# CONNECTOR_B.net
KiCad netlist of a schematic drawn in Altium Designer
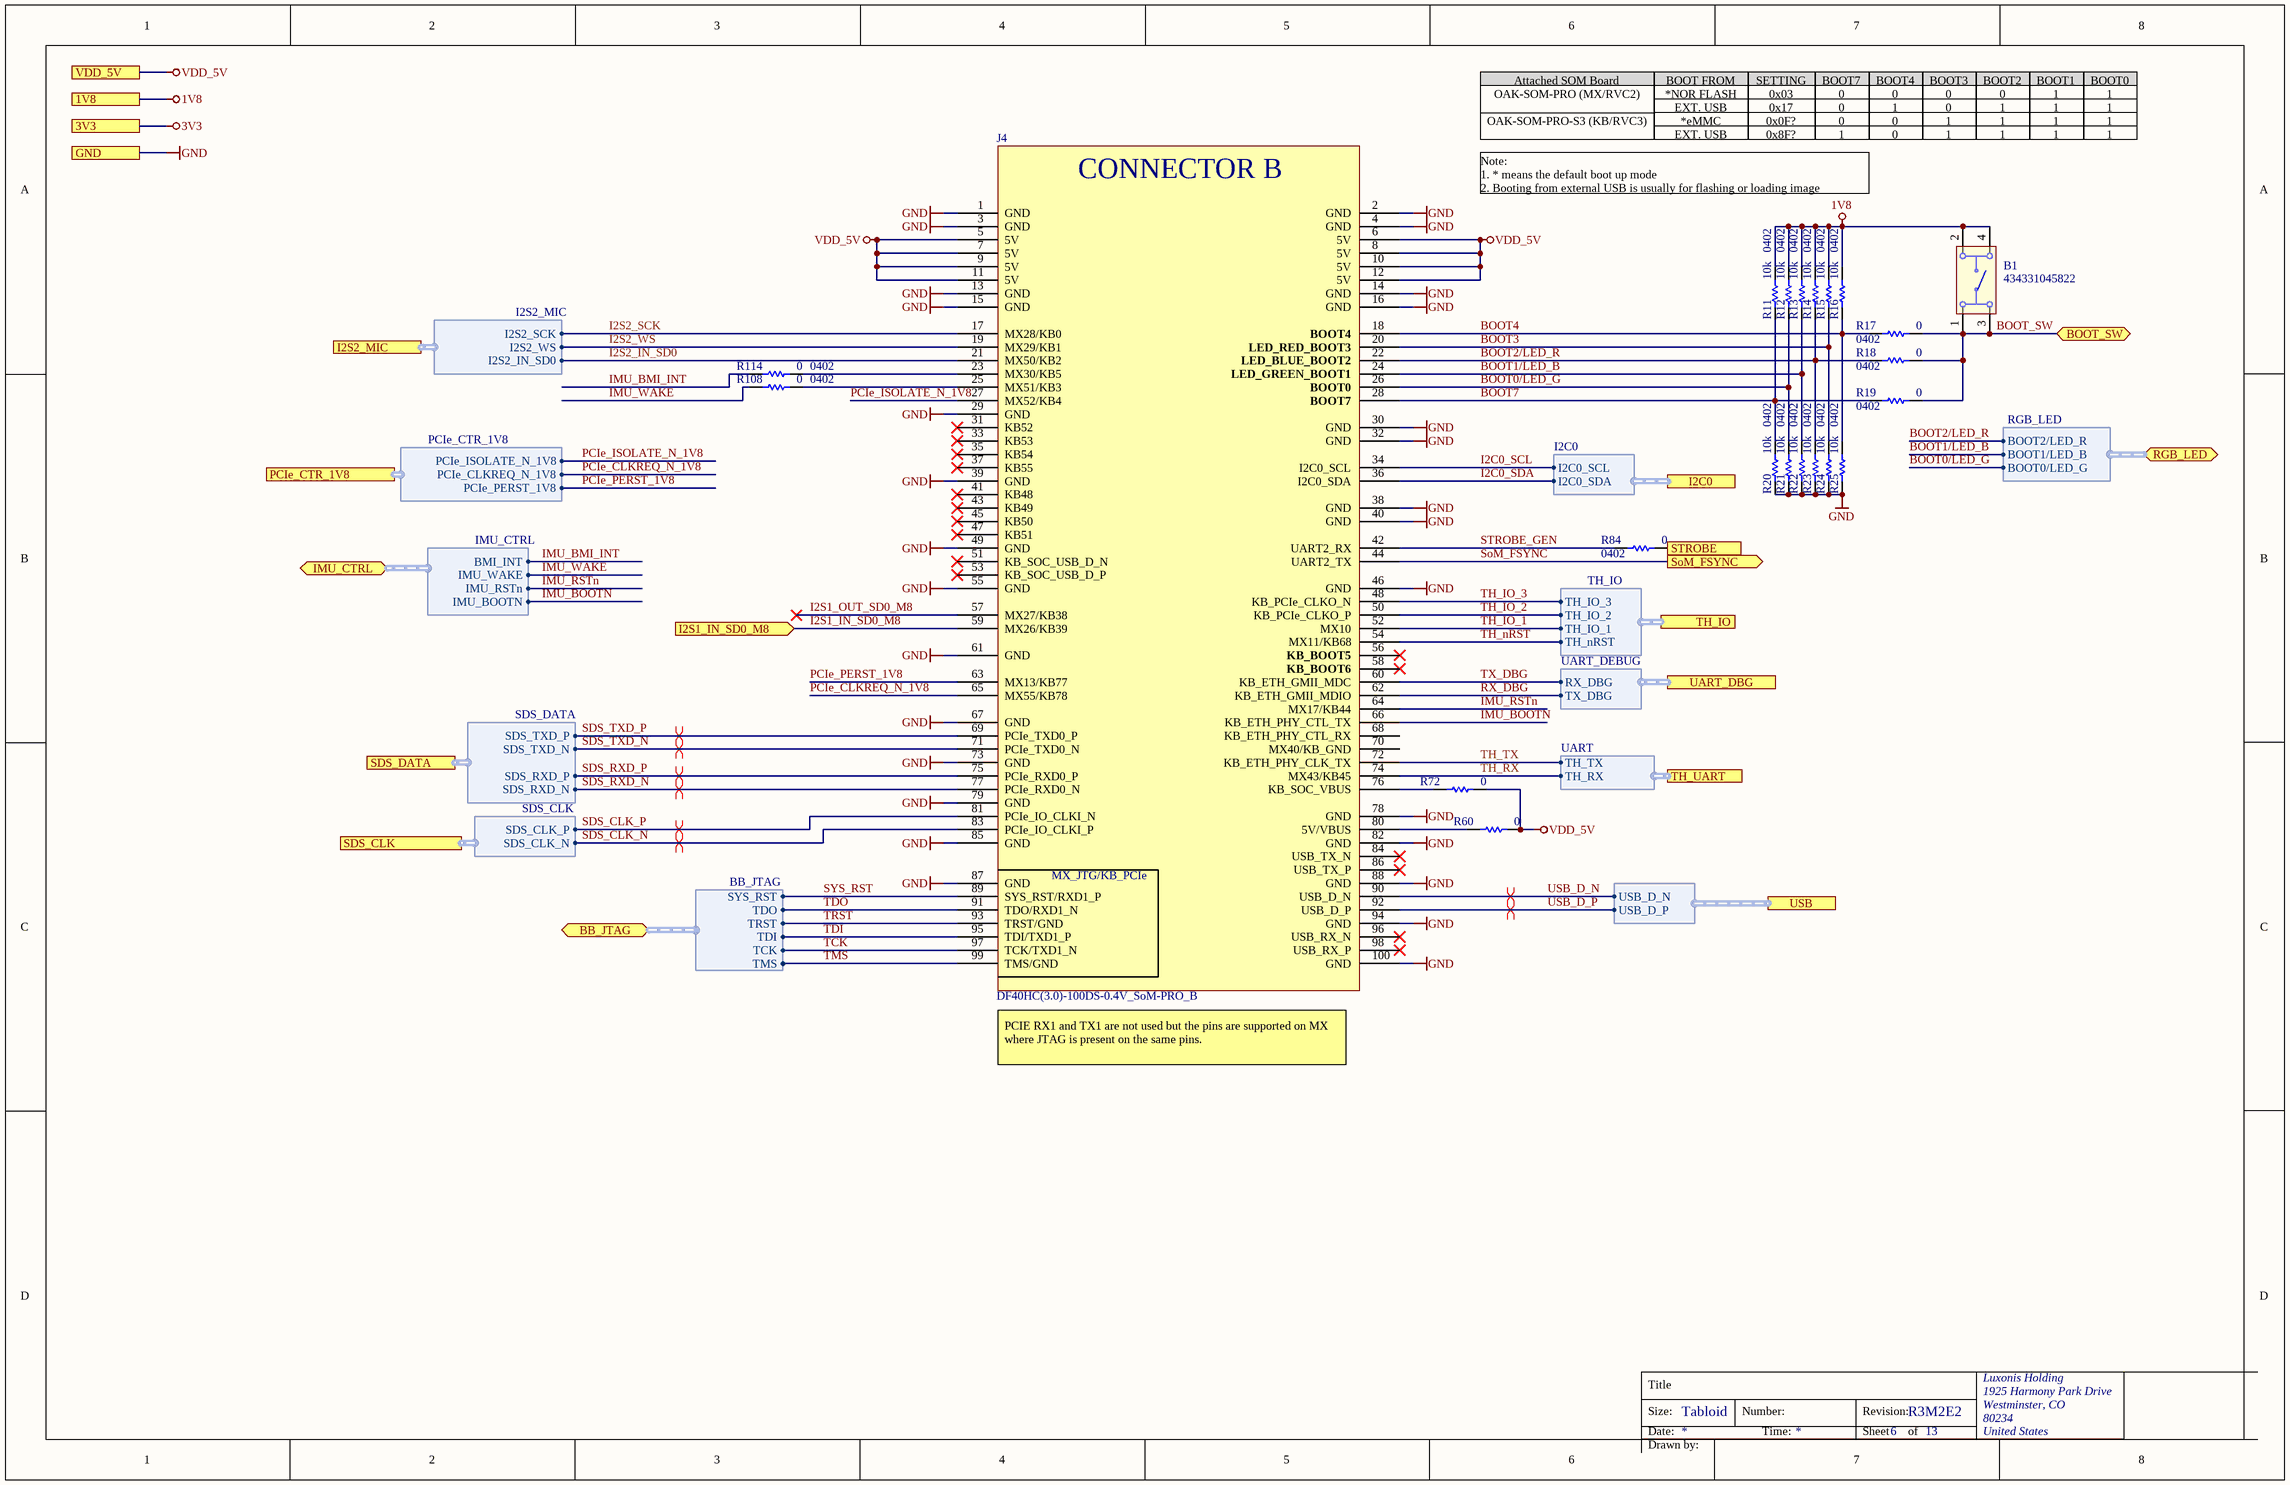
[diagram p0: CONNECTOR_B.SchDoc]

(export (version "E")
  (design (tool "Eeschema 10.0.6"))
  (components
    (comp (ref "B1")
      (value "434331045822")
      (footprint "434331045822")
      (libsource (lib "Luxonis LLC") (part "WE-TACT-SW-4"))
    )
    (comp (ref "J4")
      (value "DF40HC(3.0)-100DS-0.4V_SoM-PRO_B")
      (footprint "CON_B_BW2099_SoM_DF40HC-3.0-100DS-0.4V_minpad")
      (description "OAK-SoM-Pro_S2/S3 base board conn. B")
      (libsource (lib "Luxonis LLC") (part "DF40HC(3.0)-100DS-0.4V_SoM-PRO_B"))
    )
    (comp (ref "R11")
      (value "10k")
      (footprint "RESC0402(1005)_N")
      (description "RES SMD 10K OHM 1% 1/16W 0402")
      (fields
        (field (name "CASE/PACKAGE") "0402")
        (field (name "TOLERANCE") "1%")
        (field (name "Comment") "RC0402FR-1310KL")
      )
      (libsource (lib "Luxonis LLC") (part "RC0402FR-0722RL_1"))
    )
    (comp (ref "R12")
      (value "10k")
      (footprint "RESC0402(1005)_N")
      (description "RES SMD 10K OHM 1% 1/16W 0402")
      (fields
        (field (name "CASE/PACKAGE") "0402")
        (field (name "TOLERANCE") "1%")
        (field (name "Comment") "RC0402FR-1310KL")
      )
      (libsource (lib "Luxonis LLC") (part "RC0402FR-0722RL_1"))
    )
    (comp (ref "R13")
      (value "10k")
      (footprint "RESC0402(1005)_N")
      (description "RES SMD 10K OHM 1% 1/16W 0402")
      (fields
        (field (name "CASE/PACKAGE") "0402")
        (field (name "TOLERANCE") "1%")
        (field (name "Comment") "RC0402FR-1310KL")
      )
      (libsource (lib "Luxonis LLC") (part "RC0402FR-0722RL_1"))
    )
    (comp (ref "R14")
      (value "10k")
      (footprint "RESC0402(1005)_N")
      (description "RES SMD 10K OHM 1% 1/16W 0402")
      (fields
        (field (name "CASE/PACKAGE") "0402")
        (field (name "TOLERANCE") "1%")
        (field (name "Comment") "RC0402FR-1310KL")
      )
      (libsource (lib "Luxonis LLC") (part "RC0402FR-0722RL_1"))
    )
    (comp (ref "R15")
      (value "10k")
      (footprint "RESC0402(1005)_N")
      (description "RES SMD 10K OHM 1% 1/16W 0402")
      (fields
        (field (name "CASE/PACKAGE") "0402")
        (field (name "TOLERANCE") "1%")
        (field (name "Comment") "RC0402FR-1310KL")
      )
      (libsource (lib "Luxonis LLC") (part "RC0402FR-0722RL_1"))
    )
    (comp (ref "R16")
      (value "10k")
      (footprint "RESC0402(1005)_N")
      (description "RES SMD 10K OHM 1% 1/16W 0402")
      (fields
        (field (name "CASE/PACKAGE") "0402")
        (field (name "TOLERANCE") "1%")
        (field (name "Comment") "RC0402FR-1310KL")
      )
      (libsource (lib "Luxonis LLC") (part "RC0402FR-0722RL_1"))
    )
    (comp (ref "R17")
      (value "0")
      (footprint "RESC0402(1005)_L")
      (description "RES SMD 0 OHM 5% 1/16W 0402")
      (fields
        (field (name "CASE/PACKAGE") "0402")
        (field (name "TOLERANCE") "5%")
        (field (name "Comment") "CRCW04020000Z0ED")
      )
      (libsource (lib "Luxonis LLC") (part "Default resistor symbol"))
    )
    (comp (ref "R18")
      (value "0")
      (footprint "RESC0402(1005)_L")
      (description "RES SMD 0 OHM 5% 1/16W 0402")
      (fields
        (field (name "CASE/PACKAGE") "0402")
        (field (name "TOLERANCE") "5%")
        (field (name "Comment") "CRCW04020000Z0ED")
      )
      (libsource (lib "Luxonis LLC") (part "Default resistor symbol"))
    )
    (comp (ref "R19")
      (value "0")
      (footprint "RESC0402(1005)_L")
      (description "RES SMD 0 OHM 5% 1/16W 0402")
      (fields
        (field (name "CASE/PACKAGE") "0402")
        (field (name "TOLERANCE") "5%")
        (field (name "Comment") "CRCW04020000Z0ED")
      )
      (libsource (lib "Luxonis LLC") (part "Default resistor symbol"))
    )
    (comp (ref "R20")
      (value "10k")
      (footprint "RESC0402(1005)_N")
      (description "RES SMD 10K OHM 1% 1/16W 0402")
      (fields
        (field (name "CASE/PACKAGE") "0402")
        (field (name "TOLERANCE") "1%")
        (field (name "Comment") "RC0402FR-1310KL")
      )
      (libsource (lib "Luxonis LLC") (part "RC0402FR-0722RL_1"))
    )
    (comp (ref "R21")
      (value "10k")
      (footprint "RESC0402(1005)_N")
      (description "RES SMD 10K OHM 1% 1/16W 0402")
      (fields
        (field (name "CASE/PACKAGE") "0402")
        (field (name "TOLERANCE") "1%")
        (field (name "Comment") "RC0402FR-1310KL")
      )
      (libsource (lib "Luxonis LLC") (part "RC0402FR-0722RL_1"))
    )
    (comp (ref "R22")
      (value "10k")
      (footprint "RESC0402(1005)_N")
      (description "RES SMD 10K OHM 1% 1/16W 0402")
      (fields
        (field (name "CASE/PACKAGE") "0402")
        (field (name "TOLERANCE") "1%")
        (field (name "Comment") "RC0402FR-1310KL")
      )
      (libsource (lib "Luxonis LLC") (part "RC0402FR-0722RL_1"))
    )
    (comp (ref "R23")
      (value "10k")
      (footprint "RESC0402(1005)_N")
      (description "RES SMD 10K OHM 1% 1/16W 0402")
      (fields
        (field (name "CASE/PACKAGE") "0402")
        (field (name "TOLERANCE") "1%")
        (field (name "Comment") "RC0402FR-1310KL")
      )
      (libsource (lib "Luxonis LLC") (part "RC0402FR-0722RL_1"))
    )
    (comp (ref "R24")
      (value "10k")
      (footprint "RESC0402(1005)_N")
      (description "RES SMD 10K OHM 1% 1/16W 0402")
      (fields
        (field (name "CASE/PACKAGE") "0402")
        (field (name "TOLERANCE") "1%")
        (field (name "Comment") "RC0402FR-1310KL")
      )
      (libsource (lib "Luxonis LLC") (part "RC0402FR-0722RL_1"))
    )
    (comp (ref "R25")
      (value "10k")
      (footprint "RESC0402(1005)_N")
      (description "RES SMD 10K OHM 1% 1/16W 0402")
      (fields
        (field (name "CASE/PACKAGE") "0402")
        (field (name "TOLERANCE") "1%")
        (field (name "Comment") "RC0402FR-1310KL")
      )
      (libsource (lib "Luxonis LLC") (part "RC0402FR-0722RL_1"))
    )
    (comp (ref "R60")
      (value "0")
      (footprint "RESC0402(1005)_L")
      (description "RES SMD 0 OHM 5% 1/16W 0402")
      (fields (field (name "TOLERANCE") "5%") (field (name "Comment") "CRCW04020000Z0ED"))
      (libsource (lib "Luxonis LLC") (part "Default resistor symbol"))
    )
    (comp (ref "R72")
      (value "0")
      (footprint "RESC0402(1005)_L")
      (description "RES SMD 0 OHM 5% 1/16W 0402")
      (fields (field (name "TOLERANCE") "5%") (field (name "Comment") "CRCW04020000Z0ED"))
      (libsource (lib "Luxonis LLC") (part "Default resistor symbol"))
    )
    (comp (ref "R84")
      (value "0")
      (footprint "RESC0402(1005)_L")
      (description "RES SMD 0 OHM 5% 1/16W 0402")
      (fields
        (field (name "CASE/PACKAGE") "0402")
        (field (name "TOLERANCE") "5%")
        (field (name "Comment") "CRCW04020000Z0ED")
      )
      (libsource (lib "Luxonis LLC") (part "Default resistor symbol"))
    )
    (comp (ref "R108")
      (value "0")
      (footprint "RESC0402(1005)_L")
      (description "RES SMD 0 OHM 5% 1/16W 0402")
      (fields
        (field (name "CASE/PACKAGE") "0402")
        (field (name "TOLERANCE") "5%")
        (field (name "Comment") "CRCW04020000Z0ED")
      )
      (libsource (lib "Luxonis LLC") (part "Default resistor symbol"))
    )
    (comp (ref "R114")
      (value "0")
      (footprint "RESC0402(1005)_L")
      (description "RES SMD 0 OHM 5% 1/16W 0402")
      (fields
        (field (name "CASE/PACKAGE") "0402")
        (field (name "TOLERANCE") "5%")
        (field (name "Comment") "CRCW04020000Z0ED")
      )
      (libsource (lib "Luxonis LLC") (part "Default resistor symbol"))
    )
  )
  (nets
    (net (code "13") (name "/BOOT0{slash}LED_G") (class "Default")
      (node (ref "J4") (pin "26") (pinfunction "BOOT0_26") (pintype "passive"))
      (node (ref "R12") (pin "1") (pinfunction "1_1") (pintype "passive"))
      (node (ref "R21") (pin "2") (pinfunction "2_2") (pintype "passive"))
    )
    (net (code "14") (name "/BOOT1{slash}LED_B") (class "Default")
      (node (ref "J4") (pin "24") (pinfunction "LED_GREEN_BOOT1_24") (pintype "passive"))
      (node (ref "R13") (pin "1") (pinfunction "1_1") (pintype "passive"))
      (node (ref "R22") (pin "2") (pinfunction "2_2") (pintype "passive"))
    )
    (net (code "15") (name "/BOOT2{slash}LED_R") (class "Default")
      (node (ref "J4") (pin "22") (pinfunction "LED_BLUE_BOOT2_22") (pintype "passive"))
      (node (ref "R14") (pin "1") (pinfunction "1_1") (pintype "passive"))
      (node (ref "R18") (pin "1") (pinfunction "1_1") (pintype "passive"))
      (node (ref "R23") (pin "2") (pinfunction "2_2") (pintype "passive"))
    )
    (net (code "16") (name "/BOOT3") (class "Default")
      (node (ref "J4") (pin "20") (pinfunction "LED_RED_BOOT3_20") (pintype "passive"))
      (node (ref "R15") (pin "1") (pinfunction "1_1") (pintype "passive"))
      (node (ref "R24") (pin "2") (pinfunction "2_2") (pintype "passive"))
    )
    (net (code "17") (name "/BOOT4") (class "Default")
      (node (ref "J4") (pin "18") (pinfunction "BOOT4_18") (pintype "passive"))
      (node (ref "R16") (pin "1") (pinfunction "1_1") (pintype "passive"))
      (node (ref "R17") (pin "1") (pinfunction "1_1") (pintype "passive"))
      (node (ref "R25") (pin "2") (pinfunction "2_2") (pintype "passive"))
    )
    (net (code "18") (name "/BOOT7") (class "Default")
      (node (ref "J4") (pin "28") (pinfunction "BOOT7_28") (pintype "passive"))
      (node (ref "R11") (pin "1") (pinfunction "1_1") (pintype "passive"))
      (node (ref "R19") (pin "1") (pinfunction "1_1") (pintype "passive"))
      (node (ref "R20") (pin "2") (pinfunction "2_2") (pintype "passive"))
    )
    (net (code "19") (name "/BOOT_SW") (class "Default")
      (node (ref "B1") (pin "1") (pinfunction "1_1") (pintype "passive"))
      (node (ref "B1") (pin "3") (pinfunction "3_3") (pintype "passive"))
      (node (ref "R17") (pin "2") (pinfunction "2_2") (pintype "passive"))
      (node (ref "R18") (pin "2") (pinfunction "2_2") (pintype "passive"))
      (node (ref "R19") (pin "2") (pinfunction "2_2") (pintype "passive"))
    )
    (net (code "20") (name "/I2C0_SCL") (class "Default")
      (node (ref "J4") (pin "34") (pinfunction "I2C0_SCL_34") (pintype "passive"))
    )
    (net (code "21") (name "/I2C0_SDA") (class "Default")
      (node (ref "J4") (pin "36") (pinfunction "I2C0_SDA_36") (pintype "passive"))
    )
    (net (code "22") (name "/I2S1_IN_SD0_M8") (class "Default")
      (node (ref "J4") (pin "59") (pinfunction "MX26/KB39_59") (pintype "passive"))
    )
    (net (code "23") (name "/I2S1_OUT_SD0_M8") (class "Default")
      (node (ref "J4") (pin "57") (pinfunction "MX27/KB38_57") (pintype "passive+no_connect"))
    )
    (net (code "24") (name "/I2S2_IN_SD0") (class "Default")
      (node (ref "J4") (pin "21") (pinfunction "MX50/KB2_21") (pintype "passive"))
    )
    (net (code "25") (name "/I2S2_SCK") (class "Default")
      (node (ref "J4") (pin "17") (pinfunction "MX28/KB0_17") (pintype "passive"))
    )
    (net (code "26") (name "/I2S2_WS") (class "Default")
      (node (ref "J4") (pin "19") (pinfunction "MX29/KB1_19") (pintype "passive"))
    )
    (net (code "27") (name "/IMU_BMI_INT") (class "Default")
      (node (ref "R114") (pin "1") (pinfunction "1_1") (pintype "passive"))
    )
    (net (code "28") (name "/IMU_BOOTN") (class "Default")
      (node (ref "J4") (pin "66") (pinfunction "KB_ETH_PHY_CTL_TX_66") (pintype "passive"))
    )
    (net (code "29") (name "/IMU_RSTn") (class "Default")
      (node (ref "J4") (pin "64") (pinfunction "MX17/KB44_64") (pintype "passive"))
    )
    (net (code "30") (name "/IMU_WAKE") (class "Default")
      (node (ref "R108") (pin "1") (pinfunction "1_1") (pintype "passive"))
    )
    (net (code "31") (name "/PCIe_CLKREQ_N_1V8") (class "Default")
      (node (ref "J4") (pin "65") (pinfunction "MX55/KB78_65") (pintype "passive"))
    )
    (net (code "32") (name "/PCIe_ISOLATE_N_1V8") (class "Default")
      (node (ref "J4") (pin "27") (pinfunction "MX52/KB4_27") (pintype "passive"))
    )
    (net (code "33") (name "/PCIe_PERST_1V8") (class "Default")
      (node (ref "J4") (pin "63") (pinfunction "MX13/KB77_63") (pintype "passive"))
    )
    (net (code "34") (name "/RX_DBG") (class "Default")
      (node (ref "J4") (pin "62") (pinfunction "KB_ETH_GMII_MDIO_62") (pintype "passive"))
    )
    (net (code "35") (name "/SDS_CLK_N") (class "Default")
      (node (ref "J4") (pin "83") (pinfunction "PCIe_IO_CLKI_P_83") (pintype "passive"))
    )
    (net (code "36") (name "/SDS_CLK_P") (class "Default")
      (node (ref "J4") (pin "81") (pinfunction "PCIe_IO_CLKI_N_81") (pintype "passive"))
    )
    (net (code "37") (name "/SDS_RXD_N") (class "Default")
      (node (ref "J4") (pin "77") (pinfunction "PCIe_RXD0_N_77") (pintype "passive"))
    )
    (net (code "38") (name "/SDS_RXD_P") (class "Default")
      (node (ref "J4") (pin "75") (pinfunction "PCIe_RXD0_P_75") (pintype "passive"))
    )
    (net (code "39") (name "/SDS_TXD_N") (class "Default")
      (node (ref "J4") (pin "71") (pinfunction "PCIe_TXD0_N_71") (pintype "passive"))
    )
    (net (code "40") (name "/SDS_TXD_P") (class "Default")
      (node (ref "J4") (pin "69") (pinfunction "PCIe_TXD0_P_69") (pintype "passive"))
    )
    (net (code "41") (name "/STROBE") (class "Default")
      (node (ref "R84") (pin "2") (pinfunction "2_2") (pintype "passive"))
    )
    (net (code "42") (name "/STROBE_GEN") (class "Default")
      (node (ref "J4") (pin "42") (pinfunction "UART2_RX_42") (pintype "passive"))
      (node (ref "R84") (pin "1") (pinfunction "1_1") (pintype "passive"))
    )
    (net (code "43") (name "/SYS_RST") (class "Default")
      (node (ref "J4") (pin "89") (pinfunction "SYS_RST/RXD1_P_89") (pintype "passive"))
    )
    (net (code "44") (name "/SoM_FSYNC") (class "Default")
      (node (ref "J4") (pin "44") (pinfunction "UART2_TX_44") (pintype "passive"))
    )
    (net (code "45") (name "/TCK") (class "Default")
      (node (ref "J4") (pin "97") (pinfunction "TCK/TXD1_N_97") (pintype "passive"))
    )
    (net (code "46") (name "/TDI") (class "Default")
      (node (ref "J4") (pin "95") (pinfunction "TDI/TXD1_P_95") (pintype "passive"))
    )
    (net (code "47") (name "/TDO") (class "Default")
      (node (ref "J4") (pin "91") (pinfunction "TDO/RXD1_N_91") (pintype "passive"))
    )
    (net (code "48") (name "/TH_IO_1") (class "Default")
      (node (ref "J4") (pin "52") (pinfunction "MX10_52") (pintype "passive"))
    )
    (net (code "49") (name "/TH_IO_2") (class "Default")
      (node (ref "J4") (pin "50") (pinfunction "KB_PCIe_CLKO_P_50") (pintype "passive"))
    )
    (net (code "50") (name "/TH_IO_3") (class "Default")
      (node (ref "J4") (pin "48") (pinfunction "KB_PCIe_CLKO_N_48") (pintype "passive"))
    )
    (net (code "51") (name "/TH_RX") (class "Default")
      (node (ref "J4") (pin "74") (pinfunction "MX43/KB45_74") (pintype "passive"))
    )
    (net (code "52") (name "/TH_TX") (class "Default")
      (node (ref "J4") (pin "72") (pinfunction "KB_ETH_PHY_CLK_TX_72") (pintype "passive"))
    )
    (net (code "53") (name "/TH_nRST") (class "Default")
      (node (ref "J4") (pin "54") (pinfunction "MX11/KB68_54") (pintype "passive"))
    )
    (net (code "54") (name "/TMS") (class "Default")
      (node (ref "J4") (pin "99") (pinfunction "TMS/GND_99") (pintype "passive"))
    )
    (net (code "55") (name "/TRST") (class "Default")
      (node (ref "J4") (pin "93") (pinfunction "TRST/GND_93") (pintype "passive"))
    )
    (net (code "56") (name "/TX_DBG") (class "Default")
      (node (ref "J4") (pin "60") (pinfunction "KB_ETH_GMII_MDC_60") (pintype "passive"))
    )
    (net (code "57") (name "/USB_D_N") (class "Default")
      (node (ref "J4") (pin "90") (pinfunction "USB_D_N_90") (pintype "passive"))
    )
    (net (code "58") (name "/USB_D_P") (class "Default")
      (node (ref "J4") (pin "92") (pinfunction "USB_D_P_92") (pintype "passive"))
    )
    (net (code "71") (name "1V8") (class "Default")
      (node (ref "B1") (pin "2") (pinfunction "2_2") (pintype "passive"))
      (node (ref "B1") (pin "4") (pinfunction "4_4") (pintype "passive"))
      (node (ref "R11") (pin "2") (pinfunction "2_2") (pintype "passive"))
      (node (ref "R12") (pin "2") (pinfunction "2_2") (pintype "passive"))
      (node (ref "R13") (pin "2") (pinfunction "2_2") (pintype "passive"))
      (node (ref "R14") (pin "2") (pinfunction "2_2") (pintype "passive"))
      (node (ref "R15") (pin "2") (pinfunction "2_2") (pintype "passive"))
      (node (ref "R16") (pin "2") (pinfunction "2_2") (pintype "passive"))
    )
    (net (code "73") (name "GND") (class "Default")
      (node (ref "J4") (pin "1") (pinfunction "GND_1") (pintype "passive"))
      (node (ref "J4") (pin "100") (pinfunction "GND_100") (pintype "passive"))
      (node (ref "J4") (pin "13") (pinfunction "GND_13") (pintype "passive"))
      (node (ref "J4") (pin "14") (pinfunction "GND_14") (pintype "passive"))
      (node (ref "J4") (pin "15") (pinfunction "GND_15") (pintype "passive"))
      (node (ref "J4") (pin "16") (pinfunction "GND_16") (pintype "passive"))
      (node (ref "J4") (pin "2") (pinfunction "GND_2") (pintype "passive"))
      (node (ref "J4") (pin "29") (pinfunction "GND_29") (pintype "passive"))
      (node (ref "J4") (pin "3") (pinfunction "GND_3") (pintype "passive"))
      (node (ref "J4") (pin "30") (pinfunction "GND_30") (pintype "passive"))
      (node (ref "J4") (pin "32") (pinfunction "GND_32") (pintype "passive"))
      (node (ref "J4") (pin "38") (pinfunction "GND_38") (pintype "passive"))
      (node (ref "J4") (pin "39") (pinfunction "GND_39") (pintype "passive"))
      (node (ref "J4") (pin "4") (pinfunction "GND_4") (pintype "passive"))
      (node (ref "J4") (pin "40") (pinfunction "GND_40") (pintype "passive"))
      (node (ref "J4") (pin "46") (pinfunction "GND_46") (pintype "passive"))
      (node (ref "J4") (pin "49") (pinfunction "GND_49") (pintype "passive"))
      (node (ref "J4") (pin "55") (pinfunction "GND_55") (pintype "passive"))
      (node (ref "J4") (pin "61") (pinfunction "GND_61") (pintype "passive"))
      (node (ref "J4") (pin "67") (pinfunction "GND_67") (pintype "passive"))
      (node (ref "J4") (pin "73") (pinfunction "GND_73") (pintype "passive"))
      (node (ref "J4") (pin "78") (pinfunction "GND_78") (pintype "passive"))
      (node (ref "J4") (pin "79") (pinfunction "GND_79") (pintype "passive"))
      (node (ref "J4") (pin "82") (pinfunction "GND_82") (pintype "passive"))
      (node (ref "J4") (pin "85") (pinfunction "GND_85") (pintype "passive"))
      (node (ref "J4") (pin "87") (pinfunction "GND_87") (pintype "passive"))
      (node (ref "J4") (pin "88") (pinfunction "GND_88") (pintype "passive"))
      (node (ref "J4") (pin "94") (pinfunction "GND_94") (pintype "passive"))
      (node (ref "R20") (pin "1") (pinfunction "1_1") (pintype "passive"))
      (node (ref "R21") (pin "1") (pinfunction "1_1") (pintype "passive"))
      (node (ref "R22") (pin "1") (pinfunction "1_1") (pintype "passive"))
      (node (ref "R23") (pin "1") (pinfunction "1_1") (pintype "passive"))
      (node (ref "R24") (pin "1") (pinfunction "1_1") (pintype "passive"))
      (node (ref "R25") (pin "1") (pinfunction "1_1") (pintype "passive"))
    )
    (net (code "74") (name "Net-(J4-5V{slash}VBUS)") (class "Default")
      (node (ref "J4") (pin "80") (pinfunction "5V/VBUS_80") (pintype "passive"))
      (node (ref "R60") (pin "1") (pinfunction "1_1") (pintype "passive"))
    )
    (net (code "75") (name "Net-(J4-KB_SOC_VBUS)") (class "Default")
      (node (ref "J4") (pin "76") (pinfunction "KB_SOC_VBUS_76") (pintype "passive"))
      (node (ref "R72") (pin "1") (pinfunction "1_1") (pintype "passive"))
    )
    (net (code "76") (name "Net-(J4-MX30{slash}KB5)") (class "Default")
      (node (ref "J4") (pin "23") (pinfunction "MX30/KB5_23") (pintype "passive"))
      (node (ref "R114") (pin "2") (pinfunction "2_2") (pintype "passive"))
    )
    (net (code "77") (name "Net-(J4-MX51{slash}KB3)") (class "Default")
      (node (ref "J4") (pin "25") (pinfunction "MX51/KB3_25") (pintype "passive"))
      (node (ref "R108") (pin "2") (pinfunction "2_2") (pintype "passive"))
    )
    (net (code "78") (name "VDD_5V") (class "Default")
      (node (ref "J4") (pin "10") (pinfunction "5V_10") (pintype "passive"))
      (node (ref "J4") (pin "11") (pinfunction "5V_11") (pintype "passive"))
      (node (ref "J4") (pin "12") (pinfunction "5V_12") (pintype "passive"))
      (node (ref "J4") (pin "5") (pinfunction "5V_5") (pintype "passive"))
      (node (ref "J4") (pin "6") (pinfunction "5V_6") (pintype "passive"))
      (node (ref "J4") (pin "7") (pinfunction "5V_7") (pintype "passive"))
      (node (ref "J4") (pin "8") (pinfunction "5V_8") (pintype "passive"))
      (node (ref "J4") (pin "9") (pinfunction "5V_9") (pintype "passive"))
      (node (ref "R60") (pin "2") (pinfunction "2_2") (pintype "passive"))
      (node (ref "R72") (pin "2") (pinfunction "2_2") (pintype "passive"))
    )
    (net (code "79") (name "unconnected-(J4-KB48-Pad41)") (class "Default")
      (node (ref "J4") (pin "41") (pinfunction "KB48_41") (pintype "passive+no_connect"))
    )
    (net (code "80") (name "unconnected-(J4-KB49-Pad43)") (class "Default")
      (node (ref "J4") (pin "43") (pinfunction "KB49_43") (pintype "passive+no_connect"))
    )
    (net (code "81") (name "unconnected-(J4-KB50-Pad45)") (class "Default")
      (node (ref "J4") (pin "45") (pinfunction "KB50_45") (pintype "passive+no_connect"))
    )
    (net (code "82") (name "unconnected-(J4-KB51-Pad47)") (class "Default")
      (node (ref "J4") (pin "47") (pinfunction "KB51_47") (pintype "passive+no_connect"))
    )
    (net (code "83") (name "unconnected-(J4-KB52-Pad31)") (class "Default")
      (node (ref "J4") (pin "31") (pinfunction "KB52_31") (pintype "passive+no_connect"))
    )
    (net (code "84") (name "unconnected-(J4-KB53-Pad33)") (class "Default")
      (node (ref "J4") (pin "33") (pinfunction "KB53_33") (pintype "passive+no_connect"))
    )
    (net (code "85") (name "unconnected-(J4-KB54-Pad35)") (class "Default")
      (node (ref "J4") (pin "35") (pinfunction "KB54_35") (pintype "passive+no_connect"))
    )
    (net (code "86") (name "unconnected-(J4-KB55-Pad37)") (class "Default")
      (node (ref "J4") (pin "37") (pinfunction "KB55_37") (pintype "passive+no_connect"))
    )
    (net (code "87") (name "unconnected-(J4-KB_BOOT5-Pad56)") (class "Default")
      (node (ref "J4") (pin "56") (pinfunction "KB_BOOT5_56") (pintype "passive+no_connect"))
    )
    (net (code "88") (name "unconnected-(J4-KB_BOOT6-Pad58)") (class "Default")
      (node (ref "J4") (pin "58") (pinfunction "KB_BOOT6_58") (pintype "passive+no_connect"))
    )
    (net (code "89") (name "unconnected-(J4-KB_ETH_PHY_CTL_RX-Pad68)") (class "Default")
      (node (ref "J4") (pin "68") (pinfunction "KB_ETH_PHY_CTL_RX_68") (pintype "passive"))
    )
    (net (code "90") (name "unconnected-(J4-KB_SOC_USB_D_N-Pad51)") (class "Default")
      (node (ref "J4") (pin "51") (pinfunction "KB_SOC_USB_D_N_51") (pintype "passive+no_connect"))
    )
    (net (code "91") (name "unconnected-(J4-KB_SOC_USB_D_P-Pad53)") (class "Default")
      (node (ref "J4") (pin "53") (pinfunction "KB_SOC_USB_D_P_53") (pintype "passive+no_connect"))
    )
    (net (code "92") (name "unconnected-(J4-MX40{slash}KB_GND-Pad70)") (class "Default")
      (node (ref "J4") (pin "70") (pinfunction "MX40/KB_GND_70") (pintype "passive"))
    )
    (net (code "93") (name "unconnected-(J4-USB_RX_N-Pad96)") (class "Default")
      (node (ref "J4") (pin "96") (pinfunction "USB_RX_N_96") (pintype "passive+no_connect"))
    )
    (net (code "94") (name "unconnected-(J4-USB_RX_P-Pad98)") (class "Default")
      (node (ref "J4") (pin "98") (pinfunction "USB_RX_P_98") (pintype "passive+no_connect"))
    )
    (net (code "95") (name "unconnected-(J4-USB_TX_N-Pad84)") (class "Default")
      (node (ref "J4") (pin "84") (pinfunction "USB_TX_N_84") (pintype "passive+no_connect"))
    )
    (net (code "96") (name "unconnected-(J4-USB_TX_P-Pad86)") (class "Default")
      (node (ref "J4") (pin "86") (pinfunction "USB_TX_P_86") (pintype "passive+no_connect"))
    )
  )
)
